# Sheet_V1_0_0.net
KiCad netlist of a schematic drawn in Altium Designer
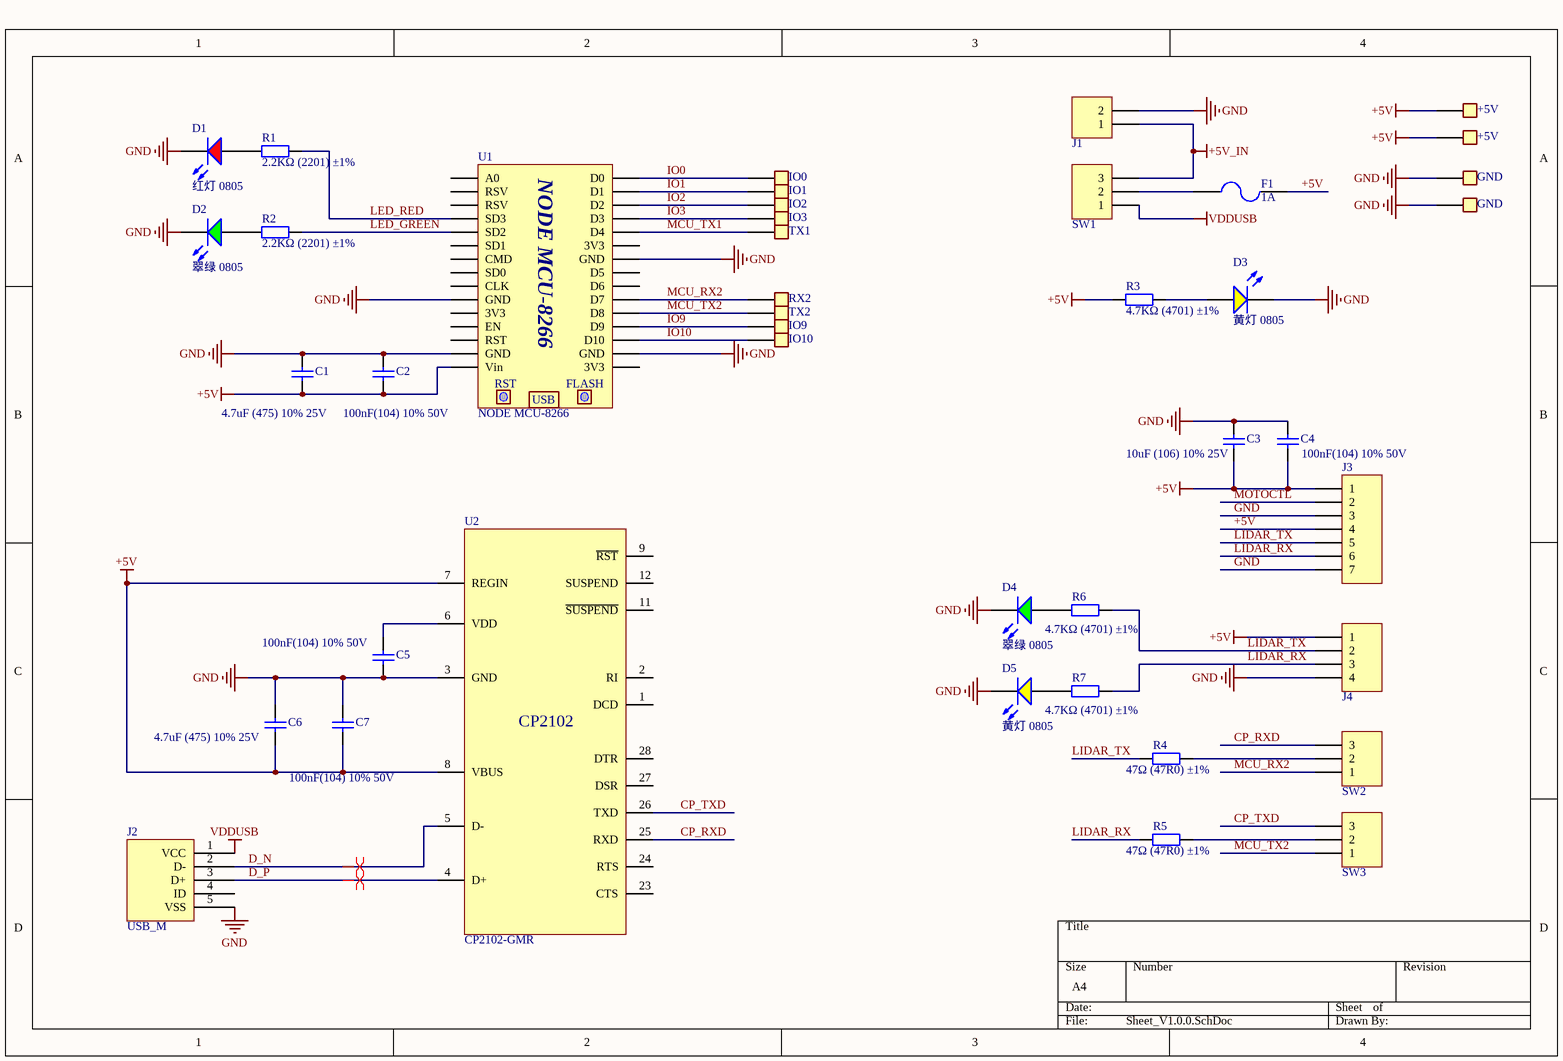
[diagram p0: Sheet_V1.0.0.SchDoc]

(export (version "E")
  (design (tool "Eeschema 10.0.6"))
  (components
    (comp (ref "C1")
      (value "4.7uF (475) 10% 25V")
      (footprint "0805_C")
      (description "贴片电容")
      (libsource (lib "Cap") (part "0805 4.7uF (475) 10% 25V"))
    )
    (comp (ref "C2")
      (value "100nF(104) 10% 50V")
      (footprint "0805_C")
      (description "贴片电容")
      (libsource (lib "Cap") (part "0805 100nF(104) 10% 50V"))
    )
    (comp (ref "C3")
      (value "10uF (106) 10% 25V")
      (footprint "0805_C")
      (description "贴片电容")
      (libsource (lib "Cap") (part "0805 10uF (106) 10% 25V"))
    )
    (comp (ref "C4")
      (value "100nF(104) 10% 50V")
      (footprint "0805_C")
      (description "贴片电容")
      (libsource (lib "Cap") (part "0805 100nF(104) 10% 50V"))
    )
    (comp (ref "C5")
      (value "100nF(104) 10% 50V")
      (footprint "0805_C")
      (description "贴片电容")
      (libsource (lib "Cap") (part "0805 100nF(104) 10% 50V"))
    )
    (comp (ref "C6")
      (value "4.7uF (475) 10% 25V")
      (footprint "0805_C")
      (description "贴片电容")
      (libsource (lib "Cap") (part "0805 4.7uF (475) 10% 25V"))
    )
    (comp (ref "C7")
      (value "100nF(104) 10% 50V")
      (footprint "0805_C")
      (description "贴片电容")
      (libsource (lib "Cap") (part "0805 100nF(104) 10% 50V"))
    )
    (comp (ref "D1")
      (value "红灯 0805")
      (footprint "0805_LED_S1")
      (description "发光二极管")
      (libsource (lib "LED") (part "0805 红灯"))
    )
    (comp (ref "D2")
      (value "翠绿 0805")
      (footprint "0805_LED_S1")
      (description "发光二极管")
      (libsource (lib "Miscellaneous Devices LC") (part "0805 翠绿"))
    )
    (comp (ref "D3")
      (value "黄灯 0805")
      (footprint "0805_LED_S1")
      (description "发光二极管")
      (libsource (lib "LED") (part "0805 黄灯"))
    )
    (comp (ref "D4")
      (value "翠绿 0805")
      (footprint "0805_LED_S1")
      (description "发光二极管")
      (libsource (lib "Miscellaneous Devices LC") (part "0805 翠绿"))
    )
    (comp (ref "D5")
      (value "黄灯 0805")
      (footprint "0805_LED_S1")
      (description "发光二极管")
      (libsource (lib "LED") (part "0805 黄灯"))
    )
    (comp (ref "F1")
      (value "1A")
      (footprint "1812")
      (description "保险丝")
      (fields (field (name "Comment") "Fuse") (field (name "PUBLISHER") "Altium Limited"))
      (libsource (lib "ghzhang") (part "Fuse 2"))
    )
    (comp (ref "J1")
      (value "Header 2")
      (footprint "MKDS3_2RMM")
      (description "接插件")
      (fields (field (name "PUBLISHER") "Altium Limited"))
      (libsource (lib "Miscellaneous Connectors") (part "Header 2"))
    )
    (comp (ref "J2")
      (value "USB_M")
      (footprint "USB-MICRO-A")
      (description "MicroUSB接口")
      (libsource (lib "ghzhang") (part "USB_M"))
    )
    (comp (ref "J3")
      (value "Header 7")
      (footprint "5267-7A")
      (description "Header, 7-Pin")
      (fields (field (name "PUBLISHER") "Altium Limited"))
      (libsource (lib "Miscellaneous Connectors") (part "Header 7"))
    )
    (comp (ref "J4")
      (value "Header 4")
      (footprint "PH2.0-4P")
      (description "接插件")
      (fields (field (name "PUBLISHER") "Altium Limited"))
      (libsource (lib "Miscellaneous Connectors") (part "Header 4"))
    )
    (comp (ref "R1")
      (value "2.2KΩ (2201) ±1%")
      (footprint "0805_R")
      (description "贴片电阻")
      (libsource (lib "Miscellaneous Devices LC") (part "0805 2.2KΩ (2201) 1%"))
    )
    (comp (ref "R2")
      (value "2.2KΩ (2201) ±1%")
      (footprint "0805_R")
      (description "贴片电阻")
      (libsource (lib "Miscellaneous Devices LC") (part "0805 2.2KΩ (2201) 1%"))
    )
    (comp (ref "R3")
      (value "4.7KΩ (4701) ±1%")
      (footprint "0805_R")
      (description "贴片电阻")
      (libsource (lib "") (part "0805 4.7KΩ (4701) 1%_1"))
    )
    (comp (ref "R4")
      (value "47Ω (47R0) ±1%")
      (footprint "0805_R")
      (description "贴片电阻")
      (libsource (lib "RES") (part "0805 47Ω (47R0) 1%"))
    )
    (comp (ref "R5")
      (value "47Ω (47R0) ±1%")
      (footprint "0805_R")
      (description "贴片电阻")
      (libsource (lib "RES") (part "0805 47Ω (47R0) 1%"))
    )
    (comp (ref "R6")
      (value "4.7KΩ (4701) ±1%")
      (footprint "0805_R")
      (description "贴片电阻")
      (libsource (lib "RES") (part "0805 4.7KΩ (4701) 1%"))
    )
    (comp (ref "R7")
      (value "4.7KΩ (4701) ±1%")
      (footprint "0805_R")
      (description "贴片电阻")
      (libsource (lib "RES") (part "0805 4.7KΩ (4701) 1%"))
    )
    (comp (ref "SW1")
      (value "Header 3")
      (footprint "HDR3X1_A")
      (description "接插件")
      (fields (field (name "PUBLISHER") "Altium Limited"))
      (libsource (lib "") (part "Header 3_1"))
    )
    (comp (ref "SW2")
      (value "Header 3")
      (footprint "HDR3X1_A")
      (description "接插件")
      (fields (field (name "PUBLISHER") "Altium Limited"))
      (libsource (lib "Miscellaneous Connectors") (part "Header 3"))
    )
    (comp (ref "SW3")
      (value "Header 3")
      (footprint "HDR3X1_A")
      (description "接插件")
      (fields (field (name "PUBLISHER") "Altium Limited"))
      (libsource (lib "Miscellaneous Connectors") (part "Header 3"))
    )
    (comp (ref "TP0") (value "IO0") (footprint "CHECK-A") (libsource (lib "原理图库") (part "TP")))
    (comp (ref "TP1") (value "IO1") (footprint "CHECK-A") (libsource (lib "原理图库") (part "TP")))
    (comp (ref "TP2") (value "IO2") (footprint "CHECK-A") (libsource (lib "原理图库") (part "TP")))
    (comp (ref "TP3") (value "IO3") (footprint "CHECK-A") (libsource (lib "原理图库") (part "TP")))
    (comp (ref "TP9") (value "IO9") (footprint "CHECK-A") (libsource (lib "原理图库") (part "TP")))
    (comp (ref "TP10") (value "IO10") (footprint "CHECK-A") (libsource (lib "原理图库") (part "TP")))
    (comp (ref "TP11") (value "TX1") (footprint "CHECK-A") (libsource (lib "原理图库") (part "TP")))
    (comp (ref "TP12") (value "RX2") (footprint "CHECK-A") (libsource (lib "原理图库") (part "TP")))
    (comp (ref "TP13") (value "TX2") (footprint "CHECK-A") (libsource (lib "原理图库") (part "TP")))
    (comp (ref "TP14") (value "+5V") (footprint "CHECK-A") (libsource (lib "原理图库") (part "TP")))
    (comp (ref "TP15") (value "+5V") (footprint "CHECK-A") (libsource (lib "原理图库") (part "TP")))
    (comp (ref "TP16") (value "GND") (footprint "CHECK-A") (libsource (lib "原理图库") (part "TP")))
    (comp (ref "TP17") (value "GND") (footprint "CHECK-A") (libsource (lib "原理图库") (part "TP")))
    (comp (ref "U1")
      (value "NODE MCU-8266")
      (footprint "ESP8266_CP2102")
      (libsource (lib "ghzhang") (part "NodeMCU_8266"))
    )
    (comp (ref "U2")
      (value "CP2102-GMR")
      (footprint "QFN-28_5x5x05P")
      (description "USB")
      (libsource (lib "IC") (part "CP2102-GMR_[C6568]"))
    )
  )
  (nets
    (net (code "1") (name "+5V") (class "Default")
      (node (ref "C1") (pin "1") (pinfunction "1_1") (pintype "passive"))
      (node (ref "C2") (pin "1") (pinfunction "1_1") (pintype "passive"))
      (node (ref "C3") (pin "1") (pinfunction "1_1") (pintype "passive"))
      (node (ref "C4") (pin "1") (pinfunction "1_1") (pintype "passive"))
      (node (ref "C6") (pin "1") (pinfunction "1_1") (pintype "passive"))
      (node (ref "C7") (pin "1") (pinfunction "1_1") (pintype "passive"))
      (node (ref "F1") (pin "2") (pinfunction "2_2") (pintype "passive"))
      (node (ref "J3") (pin "1") (pinfunction "1_1") (pintype "passive"))
      (node (ref "J3") (pin "4") (pinfunction "4_4") (pintype "passive"))
      (node (ref "J4") (pin "1") (pinfunction "1_1") (pintype "passive"))
      (node (ref "R3") (pin "1") (pinfunction "1_1") (pintype "passive"))
      (node (ref "TP14") (pin "1") (pintype "passive"))
      (node (ref "TP15") (pin "1") (pintype "passive"))
      (node (ref "U1") (pin "15") (pinfunction "Vin_15") (pintype "passive"))
      (node (ref "U2") (pin "7") (pinfunction "REGIN_7") (pintype "passive"))
      (node (ref "U2") (pin "8") (pinfunction "VBUS_8") (pintype "passive"))
    )
    (net (code "2") (name "+5V_IN") (class "Default")
      (node (ref "J1") (pin "1") (pinfunction "1_1") (pintype "passive"))
      (node (ref "SW1") (pin "3") (pinfunction "3_3") (pintype "passive"))
    )
    (net (code "3") (name "/CP_RXD") (class "Default")
      (node (ref "SW2") (pin "3") (pinfunction "3_3") (pintype "passive"))
      (node (ref "U2") (pin "25") (pinfunction "RXD_25") (pintype "passive"))
    )
    (net (code "4") (name "/CP_TXD") (class "Default")
      (node (ref "SW3") (pin "3") (pinfunction "3_3") (pintype "passive"))
      (node (ref "U2") (pin "26") (pinfunction "TXD_26") (pintype "passive"))
    )
    (net (code "5") (name "/D_N") (class "Default")
      (node (ref "J2") (pin "2") (pinfunction "D-_2") (pintype "passive"))
      (node (ref "U2") (pin "5") (pinfunction "D-_5") (pintype "passive"))
    )
    (net (code "6") (name "/D_P") (class "Default")
      (node (ref "J2") (pin "3") (pinfunction "D+_3") (pintype "passive"))
      (node (ref "U2") (pin "4") (pinfunction "D+_4") (pintype "passive"))
    )
    (net (code "7") (name "/IO0") (class "Default")
      (node (ref "TP0") (pin "1") (pintype "passive"))
      (node (ref "U1") (pin "30") (pinfunction "D0_30") (pintype "passive"))
    )
    (net (code "8") (name "/IO1") (class "Default")
      (node (ref "TP1") (pin "1") (pintype "passive"))
      (node (ref "U1") (pin "29") (pinfunction "D1_29") (pintype "passive"))
    )
    (net (code "9") (name "/IO2") (class "Default")
      (node (ref "TP2") (pin "1") (pintype "passive"))
      (node (ref "U1") (pin "28") (pinfunction "D2_28") (pintype "passive"))
    )
    (net (code "10") (name "/IO3") (class "Default")
      (node (ref "TP3") (pin "1") (pintype "passive"))
      (node (ref "U1") (pin "27") (pinfunction "D3_27") (pintype "passive"))
    )
    (net (code "11") (name "/IO9") (class "Default")
      (node (ref "TP9") (pin "1") (pintype "passive"))
      (node (ref "U1") (pin "19") (pinfunction "D9_19") (pintype "passive"))
    )
    (net (code "12") (name "/IO10") (class "Default")
      (node (ref "TP10") (pin "1") (pintype "passive"))
      (node (ref "U1") (pin "18") (pinfunction "D10_18") (pintype "passive"))
    )
    (net (code "13") (name "/LED_GREEN") (class "Default")
      (node (ref "R2") (pin "1") (pinfunction "1_1") (pintype "passive"))
      (node (ref "U1") (pin "5") (pinfunction "SD2_5") (pintype "passive"))
    )
    (net (code "14") (name "/LED_RED") (class "Default")
      (node (ref "R1") (pin "1") (pinfunction "1_1") (pintype "passive"))
      (node (ref "U1") (pin "4") (pinfunction "SD3_4") (pintype "passive"))
    )
    (net (code "15") (name "/LIDAR_RX") (class "Default")
      (node (ref "J3") (pin "6") (pinfunction "6_6") (pintype "passive"))
      (node (ref "J4") (pin "3") (pinfunction "3_3") (pintype "passive"))
      (node (ref "R5") (pin "1") (pinfunction "1_1") (pintype "passive"))
      (node (ref "R7") (pin "1") (pinfunction "1_1") (pintype "passive"))
    )
    (net (code "16") (name "/LIDAR_TX") (class "Default")
      (node (ref "J3") (pin "5") (pinfunction "5_5") (pintype "passive"))
      (node (ref "J4") (pin "2") (pinfunction "2_2") (pintype "passive"))
      (node (ref "R4") (pin "1") (pinfunction "1_1") (pintype "passive"))
      (node (ref "R6") (pin "1") (pinfunction "1_1") (pintype "passive"))
    )
    (net (code "17") (name "/MCU_RX2") (class "Default")
      (node (ref "SW2") (pin "1") (pinfunction "1_1") (pintype "passive"))
      (node (ref "TP12") (pin "1") (pintype "passive"))
      (node (ref "U1") (pin "21") (pinfunction "D7_21") (pintype "passive"))
    )
    (net (code "18") (name "/MCU_TX1") (class "Default")
      (node (ref "TP11") (pin "1") (pintype "passive"))
      (node (ref "U1") (pin "26") (pinfunction "D4_26") (pintype "passive"))
    )
    (net (code "19") (name "/MCU_TX2") (class "Default")
      (node (ref "SW3") (pin "1") (pinfunction "1_1") (pintype "passive"))
      (node (ref "TP13") (pin "1") (pintype "passive"))
      (node (ref "U1") (pin "20") (pinfunction "D8_20") (pintype "passive"))
    )
    (net (code "20") (name "/MOTOCTL") (class "Default")
      (node (ref "J3") (pin "2") (pinfunction "2_2") (pintype "passive"))
    )
    (net (code "21") (name "GND") (class "Default")
      (node (ref "C1") (pin "2") (pinfunction "2_2") (pintype "passive"))
      (node (ref "C2") (pin "2") (pinfunction "2_2") (pintype "passive"))
      (node (ref "C3") (pin "2") (pinfunction "2_2") (pintype "passive"))
      (node (ref "C4") (pin "2") (pinfunction "2_2") (pintype "passive"))
      (node (ref "C5") (pin "1") (pinfunction "1_1") (pintype "passive"))
      (node (ref "C6") (pin "2") (pinfunction "2_2") (pintype "passive"))
      (node (ref "C7") (pin "2") (pinfunction "2_2") (pintype "passive"))
      (node (ref "D1") (pin "K") (pinfunction "K_K") (pintype "passive"))
      (node (ref "D2") (pin "K") (pinfunction "K_K") (pintype "passive"))
      (node (ref "D3") (pin "K") (pinfunction "K_K") (pintype "passive"))
      (node (ref "D4") (pin "K") (pinfunction "K_K") (pintype "passive"))
      (node (ref "D5") (pin "K") (pinfunction "K_K") (pintype "passive"))
      (node (ref "J1") (pin "2") (pinfunction "2_2") (pintype "passive"))
      (node (ref "J2") (pin "5") (pinfunction "VSS_5") (pintype "passive"))
      (node (ref "J3") (pin "3") (pinfunction "3_3") (pintype "passive"))
      (node (ref "J3") (pin "7") (pinfunction "7_7") (pintype "passive"))
      (node (ref "J4") (pin "4") (pinfunction "4_4") (pintype "passive"))
      (node (ref "TP16") (pin "1") (pintype "passive"))
      (node (ref "TP17") (pin "1") (pintype "passive"))
      (node (ref "U1") (pin "10") (pinfunction "GND_10") (pintype "passive"))
      (node (ref "U1") (pin "14") (pinfunction "GND_14") (pintype "passive"))
      (node (ref "U1") (pin "17") (pinfunction "GND_17") (pintype "passive"))
      (node (ref "U1") (pin "24") (pinfunction "GND_24") (pintype "passive"))
      (node (ref "U2") (pin "3") (pinfunction "GND_3") (pintype "passive"))
    )
    (net (code "22") (name "Net-(D1-PadA)") (class "Default")
      (node (ref "D1") (pin "A") (pinfunction "A_A") (pintype "passive"))
      (node (ref "R1") (pin "2") (pinfunction "2_2") (pintype "passive"))
    )
    (net (code "23") (name "Net-(D2-PadA)") (class "Default")
      (node (ref "D2") (pin "A") (pinfunction "A_A") (pintype "passive"))
      (node (ref "R2") (pin "2") (pinfunction "2_2") (pintype "passive"))
    )
    (net (code "24") (name "Net-(D3-PadA)") (class "Default")
      (node (ref "D3") (pin "A") (pinfunction "A_A") (pintype "passive"))
      (node (ref "R3") (pin "2") (pinfunction "2_2") (pintype "passive"))
    )
    (net (code "25") (name "Net-(D4-PadA)") (class "Default")
      (node (ref "D4") (pin "A") (pinfunction "A_A") (pintype "passive"))
      (node (ref "R6") (pin "2") (pinfunction "2_2") (pintype "passive"))
    )
    (net (code "26") (name "Net-(D5-PadA)") (class "Default")
      (node (ref "D5") (pin "A") (pinfunction "A_A") (pintype "passive"))
      (node (ref "R7") (pin "2") (pinfunction "2_2") (pintype "passive"))
    )
    (net (code "27") (name "Net-(F1-Pad1)") (class "Default")
      (node (ref "F1") (pin "1") (pinfunction "1_1") (pintype "passive"))
      (node (ref "SW1") (pin "2") (pinfunction "2_2") (pintype "passive"))
    )
    (net (code "28") (name "Net-(R4-Pad2)") (class "Default")
      (node (ref "R4") (pin "2") (pinfunction "2_2") (pintype "passive"))
      (node (ref "SW2") (pin "2") (pinfunction "2_2") (pintype "passive"))
    )
    (net (code "29") (name "Net-(R5-Pad2)") (class "Default")
      (node (ref "R5") (pin "2") (pinfunction "2_2") (pintype "passive"))
      (node (ref "SW3") (pin "2") (pinfunction "2_2") (pintype "passive"))
    )
    (net (code "30") (name "Net-(U2-VDD)") (class "Default")
      (node (ref "C5") (pin "2") (pinfunction "2_2") (pintype "passive"))
      (node (ref "U2") (pin "6") (pinfunction "VDD_6") (pintype "passive"))
    )
    (net (code "31") (name "VDDUSB") (class "Default")
      (node (ref "J2") (pin "1") (pinfunction "VCC_1") (pintype "passive"))
      (node (ref "SW1") (pin "1") (pinfunction "1_1") (pintype "passive"))
    )
    (net (code "32") (name "unconnected-(J2-ID-Pad4)") (class "Default")
      (node (ref "J2") (pin "4") (pinfunction "ID_4") (pintype "passive"))
    )
    (net (code "33") (name "unconnected-(U1-3V3-Pad11)") (class "Default")
      (node (ref "U1") (pin "11") (pinfunction "3V3_11") (pintype "passive"))
    )
    (net (code "34") (name "unconnected-(U1-3V3-Pad16)") (class "Default")
      (node (ref "U1") (pin "16") (pinfunction "3V3_16") (pintype "passive"))
    )
    (net (code "35") (name "unconnected-(U1-3V3-Pad25)") (class "Default")
      (node (ref "U1") (pin "25") (pinfunction "3V3_25") (pintype "passive"))
    )
    (net (code "36") (name "unconnected-(U1-A0-Pad1)") (class "Default")
      (node (ref "U1") (pin "1") (pinfunction "A0_1") (pintype "passive"))
    )
    (net (code "37") (name "unconnected-(U1-CLK-Pad9)") (class "Default")
      (node (ref "U1") (pin "9") (pinfunction "CLK_9") (pintype "passive"))
    )
    (net (code "38") (name "unconnected-(U1-CMD-Pad7)") (class "Default")
      (node (ref "U1") (pin "7") (pinfunction "CMD_7") (pintype "passive"))
    )
    (net (code "39") (name "unconnected-(U1-D5-Pad23)") (class "Default")
      (node (ref "U1") (pin "23") (pinfunction "D5_23") (pintype "passive"))
    )
    (net (code "40") (name "unconnected-(U1-D6-Pad22)") (class "Default")
      (node (ref "U1") (pin "22") (pinfunction "D6_22") (pintype "passive"))
    )
    (net (code "41") (name "unconnected-(U1-EN-Pad12)") (class "Default")
      (node (ref "U1") (pin "12") (pinfunction "EN_12") (pintype "passive"))
    )
    (net (code "42") (name "unconnected-(U1-RST-Pad13)") (class "Default")
      (node (ref "U1") (pin "13") (pinfunction "RST_13") (pintype "passive"))
    )
    (net (code "43") (name "unconnected-(U1-RSV-Pad2)") (class "Default")
      (node (ref "U1") (pin "2") (pinfunction "RSV_2") (pintype "passive"))
    )
    (net (code "44") (name "unconnected-(U1-RSV-Pad3)") (class "Default")
      (node (ref "U1") (pin "3") (pinfunction "RSV_3") (pintype "passive"))
    )
    (net (code "45") (name "unconnected-(U1-SD0-Pad8)") (class "Default")
      (node (ref "U1") (pin "8") (pinfunction "SD0_8") (pintype "passive"))
    )
    (net (code "46") (name "unconnected-(U1-SD1-Pad6)") (class "Default")
      (node (ref "U1") (pin "6") (pinfunction "SD1_6") (pintype "passive"))
    )
    (net (code "47") (name "unconnected-(U2-CTS-Pad23)") (class "Default")
      (node (ref "U2") (pin "23") (pinfunction "CTS_23") (pintype "passive"))
    )
    (net (code "48") (name "unconnected-(U2-DCD-Pad1)") (class "Default")
      (node (ref "U2") (pin "1") (pinfunction "DCD_1") (pintype "passive"))
    )
    (net (code "49") (name "unconnected-(U2-DSR-Pad27)") (class "Default")
      (node (ref "U2") (pin "27") (pinfunction "DSR_27") (pintype "passive"))
    )
    (net (code "50") (name "unconnected-(U2-DTR-Pad28)") (class "Default")
      (node (ref "U2") (pin "28") (pinfunction "DTR_28") (pintype "passive"))
    )
    (net (code "51") (name "unconnected-(U2-RI-Pad2)") (class "Default")
      (node (ref "U2") (pin "2") (pinfunction "RI_2") (pintype "passive"))
    )
    (net (code "52") (name "unconnected-(U2-RTS-Pad24)") (class "Default")
      (node (ref "U2") (pin "24") (pinfunction "RTS_24") (pintype "passive"))
    )
    (net (code "53") (name "unconnected-(U2-SUSPEND-Pad12)") (class "Default")
      (node (ref "U2") (pin "12") (pinfunction "SUSPEND_12") (pintype "passive"))
    )
    (net (code "54") (name "unconnected-(U2-~{RST}-Pad9)") (class "Default")
      (node (ref "U2") (pin "9") (pinfunction "~{RST}_9") (pintype "passive"))
    )
    (net (code "55") (name "unconnected-(U2-~{SUSPEND}-Pad11)") (class "Default")
      (node (ref "U2") (pin "11") (pinfunction "~{SUSPEND}_11") (pintype "passive"))
    )
  )
)
